# 2_5_0_PCB_LY-2X5_0-V1_1.net
KiCad netlist of a schematic drawn in EasyEDA Pro
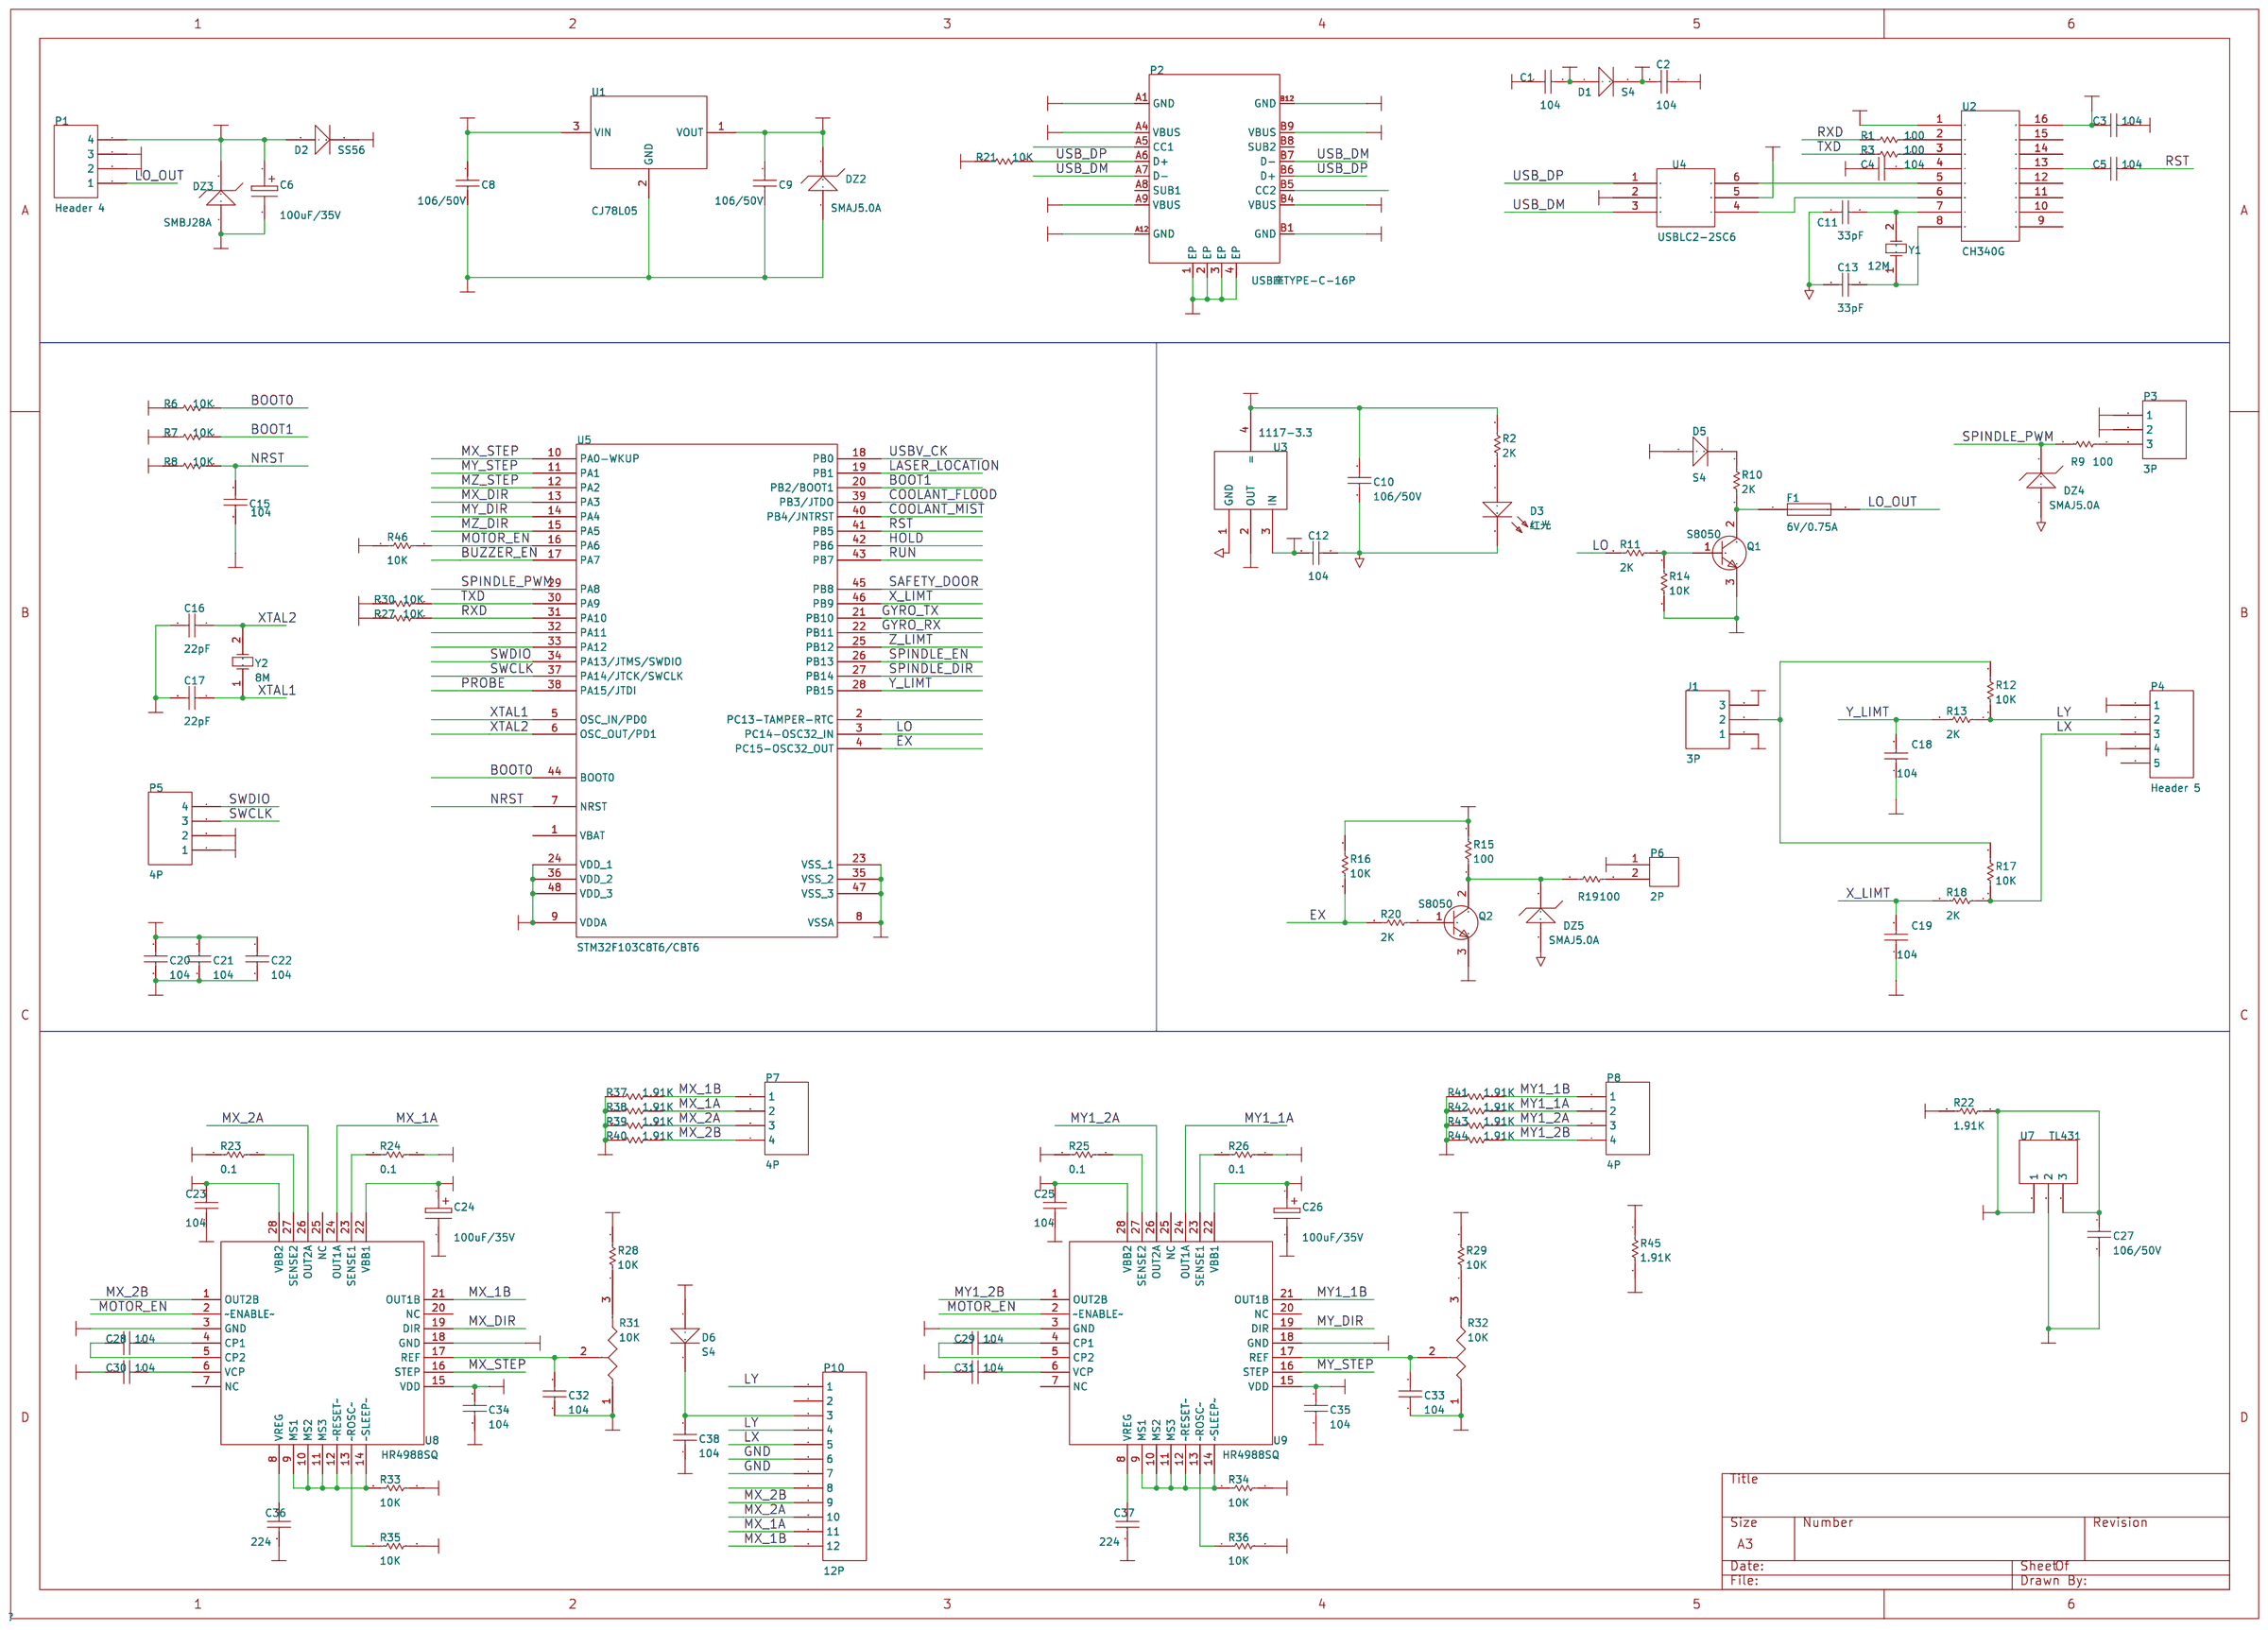
[diagram p0: schematic sheet]

(export (version "E")
  (design (tool "Eeschema 10.0.6"))
  (components
    (comp (ref "C1")
      (value "104")
      (footprint "easyedapro:0603C")
      (description "Capacitor (Semiconductor SIM Model)")
      (libsource (lib "easyedapro") (part "Cap Semi"))
    )
    (comp (ref "C2")
      (value "104")
      (footprint "easyedapro:0603C")
      (description "Capacitor (Semiconductor SIM Model)")
      (libsource (lib "easyedapro") (part "Cap Semi"))
    )
    (comp (ref "C3")
      (value "104")
      (footprint "easyedapro:0603C")
      (description "Capacitor (Semiconductor SIM Model)")
      (libsource (lib "easyedapro") (part "Cap Semi"))
    )
    (comp (ref "C4")
      (value "104")
      (footprint "easyedapro:0603C")
      (description "Capacitor (Semiconductor SIM Model)")
      (libsource (lib "easyedapro") (part "Cap Semi"))
    )
    (comp (ref "C5")
      (value "104")
      (footprint "easyedapro:0603C")
      (description "Capacitor (Semiconductor SIM Model)")
      (libsource (lib "easyedapro") (part "Cap Semi"))
    )
    (comp (ref "C6")
      (value "100uF/35V")
      (footprint "easyedapro:电容插件M6.3")
      (libsource (lib "easyedapro") (part "ELECTRO1"))
    )
    (comp (ref "C8")
      (value "106/50V")
      (footprint "easyedapro:0603C")
      (description "Capacitor (Semiconductor SIM Model)")
      (libsource (lib "easyedapro") (part "Cap Semi"))
    )
    (comp (ref "C9")
      (value "106/50V")
      (footprint "easyedapro:0603C")
      (description "Capacitor (Semiconductor SIM Model)")
      (libsource (lib "easyedapro") (part "Cap Semi"))
    )
    (comp (ref "C10")
      (value "106/50V")
      (footprint "easyedapro:0603C")
      (description "Capacitor (Semiconductor SIM Model)")
      (libsource (lib "easyedapro") (part "Cap Semi"))
    )
    (comp (ref "C11")
      (value "18pF")
      (footprint "easyedapro:0603C")
      (description "Capacitor (Semiconductor SIM Model)")
      (libsource (lib "easyedapro") (part "Cap Semi"))
    )
    (comp (ref "C12")
      (value "104")
      (footprint "easyedapro:0603C")
      (description "Capacitor (Semiconductor SIM Model)")
      (libsource (lib "easyedapro") (part "Cap Semi"))
    )
    (comp (ref "C13")
      (value "18pF")
      (footprint "easyedapro:0603C")
      (description "Capacitor (Semiconductor SIM Model)")
      (libsource (lib "easyedapro") (part "Cap Semi"))
    )
    (comp (ref "C15")
      (value "104")
      (footprint "easyedapro:0603C")
      (description "Capacitor (Semiconductor SIM Model)")
      (libsource (lib "easyedapro") (part "Cap Semi"))
    )
    (comp (ref "C16")
      (value "100pF")
      (footprint "easyedapro:0603C")
      (description "Capacitor (Semiconductor SIM Model)")
      (libsource (lib "easyedapro") (part "Cap Semi"))
    )
    (comp (ref "C17")
      (value "100pF")
      (footprint "easyedapro:0603C")
      (description "Capacitor (Semiconductor SIM Model)")
      (libsource (lib "easyedapro") (part "Cap Semi"))
    )
    (comp (ref "C18")
      (value "104")
      (footprint "easyedapro:0603C")
      (libsource (lib "easyedapro") (part "CAP"))
    )
    (comp (ref "C19")
      (value "104")
      (footprint "easyedapro:0603C")
      (libsource (lib "easyedapro") (part "CAP"))
    )
    (comp (ref "C20")
      (value "104")
      (footprint "easyedapro:0603C")
      (libsource (lib "easyedapro") (part "CAP"))
    )
    (comp (ref "C21")
      (value "104")
      (footprint "easyedapro:0603C")
      (libsource (lib "easyedapro") (part "CAP"))
    )
    (comp (ref "C22")
      (value "104")
      (footprint "easyedapro:0603C")
      (libsource (lib "easyedapro") (part "CAP"))
    )
    (comp (ref "C23")
      (value "104")
      (footprint "easyedapro:0603C")
      (description "Capacitor (Semiconductor SIM Model)")
      (libsource (lib "easyedapro") (part "Cap Semi"))
    )
    (comp (ref "C24")
      (value "100uF/35V")
      (footprint "easyedapro:电容插件M6.3")
      (libsource (lib "easyedapro") (part "ELECTRO1"))
    )
    (comp (ref "C25")
      (value "104")
      (footprint "easyedapro:0603C")
      (description "Capacitor (Semiconductor SIM Model)")
      (libsource (lib "easyedapro") (part "Cap Semi"))
    )
    (comp (ref "C26")
      (value "100uF/35V")
      (footprint "easyedapro:电容插件M6.3")
      (libsource (lib "easyedapro") (part "ELECTRO1"))
    )
    (comp (ref "C27")
      (value "106/50V")
      (footprint "easyedapro:0603C")
      (description "Capacitor (Semiconductor SIM Model)")
      (libsource (lib "easyedapro") (part "Cap Semi"))
    )
    (comp (ref "C28")
      (value "104")
      (footprint "easyedapro:0603C")
      (libsource (lib "easyedapro") (part "CAP"))
    )
    (comp (ref "C29")
      (value "104")
      (footprint "easyedapro:0603C")
      (libsource (lib "easyedapro") (part "CAP"))
    )
    (comp (ref "C30")
      (value "104")
      (footprint "easyedapro:0603C")
      (libsource (lib "easyedapro") (part "CAP"))
    )
    (comp (ref "C31")
      (value "104")
      (footprint "easyedapro:0603C")
      (libsource (lib "easyedapro") (part "CAP"))
    )
    (comp (ref "C32")
      (value "104")
      (footprint "easyedapro:0603C")
      (libsource (lib "easyedapro") (part "CAP"))
    )
    (comp (ref "C33")
      (value "104")
      (footprint "easyedapro:0603C")
      (libsource (lib "easyedapro") (part "CAP"))
    )
    (comp (ref "C34")
      (value "104")
      (footprint "easyedapro:0603C")
      (libsource (lib "easyedapro") (part "CAP"))
    )
    (comp (ref "C35")
      (value "104")
      (footprint "easyedapro:0603C")
      (libsource (lib "easyedapro") (part "CAP"))
    )
    (comp (ref "C36")
      (value "224")
      (footprint "easyedapro:0603C")
      (libsource (lib "easyedapro") (part "CAP"))
    )
    (comp (ref "C37")
      (value "224")
      (footprint "easyedapro:0603C")
      (libsource (lib "easyedapro") (part "CAP"))
    )
    (comp (ref "C38")
      (value "104")
      (footprint "easyedapro:0603C")
      (description "Capacitor (Semiconductor SIM Model)")
      (libsource (lib "easyedapro") (part "Cap Semi"))
    )
    (comp (ref "D1") (value "S4") (footprint "easyedapro:SMA") (libsource (lib "easyedapro") (part "1N4148")))
    (comp (ref "D2")
      (value "SS56")
      (footprint "easyedapro:SMA")
      (libsource (lib "easyedapro") (part "1N4148"))
    )
    (comp (ref "D3")
      (value "红光")
      (footprint "easyedapro:0603LED")
      (libsource (lib "easyedapro") (part "LED"))
    )
    (comp (ref "D5") (value "S4") (footprint "easyedapro:SMA") (libsource (lib "easyedapro") (part "1N4148")))
    (comp (ref "D6") (value "S4") (footprint "easyedapro:SMA") (libsource (lib "easyedapro") (part "1N4148")))
    (comp (ref "DZ2")
      (value "SMAJ5.0A")
      (footprint "easyedapro:SMA")
      (libsource (lib "easyedapro") (part "稳压二极管"))
    )
    (comp (ref "DZ3")
      (value "SMBJ28A")
      (footprint "easyedapro:SMA")
      (libsource (lib "easyedapro") (part "稳压二极管"))
    )
    (comp (ref "DZ4")
      (value "SMAJ5.0A")
      (footprint "easyedapro:SMA")
      (libsource (lib "easyedapro") (part "稳压二极管"))
    )
    (comp (ref "DZ5")
      (value "SMAJ5.0A")
      (footprint "easyedapro:SMA")
      (libsource (lib "easyedapro") (part "稳压二极管"))
    )
    (comp (ref "F1")
      (value "6V/0.75A")
      (footprint "easyedapro:1206R")
      (description "保险丝")
      (libsource (lib "easyedapro") (part "FUSE1"))
    )
    (comp (ref "J1")
      (value "3P")
      (footprint "easyedapro:HDR1X3_CON")
      (libsource (lib "easyedapro") (part "3P"))
    )
    (comp (ref "P1")
      (value "Header 4")
      (footprint "easyedapro:VH3.96-4P直插座")
      (description "Header, 4-Pin")
      (libsource (lib "easyedapro") (part "Header 4"))
    )
    (comp (ref "P2")
      (value "USB座TYPE-C-16P")
      (footprint "easyedapro:USB-TYPE-C-16P")
      (fields
        (field (name "Manufacturer Part") "KH-TYPE-C-16P-T")
        (field (name "Manufacturer") "Shenzhen Kinghelm Elec")
      )
      (libsource (lib "easyedapro") (part "USB座TYPE-C-16P"))
    )
    (comp (ref "P3")
      (value "3P")
      (footprint "easyedapro:HDR1X3_CON")
      (libsource (lib "easyedapro") (part "3P"))
    )
    (comp (ref "P4")
      (value "Header 5")
      (footprint "easyedapro:HDR1X5_CON")
      (description "Header, 5-Pin")
      (libsource (lib "easyedapro") (part "Header 5"))
    )
    (comp (ref "P5") (value "4P") (footprint "easyedapro:SIP4") (libsource (lib "easyedapro") (part "4P")))
    (comp (ref "P6")
      (value "2P")
      (footprint "easyedapro:HDR1X2_CON")
      (libsource (lib "easyedapro") (part "2P"))
    )
    (comp (ref "P7") (value "4P") (footprint "easyedapro:SIP4") (libsource (lib "easyedapro") (part "4P")))
    (comp (ref "P8") (value "4P") (footprint "easyedapro:SIP4") (libsource (lib "easyedapro") (part "4P")))
    (comp (ref "P10")
      (value "12P")
      (footprint "easyedapro:FFC/FPC直插座-1.25-12P")
      (libsource (lib "easyedapro") (part "12P"))
    )
    (comp (ref "Q1")
      (value "S8050")
      (footprint "easyedapro:SOT-23")
      (libsource (lib "easyedapro") (part "NPN"))
    )
    (comp (ref "Q2")
      (value "S8050")
      (footprint "easyedapro:SOT-23")
      (libsource (lib "easyedapro") (part "NPN"))
    )
    (comp (ref "R1")
      (value "100")
      (footprint "easyedapro:1206R")
      (description "Resistor")
      (libsource (lib "easyedapro") (part "RES"))
    )
    (comp (ref "R2")
      (value "2K")
      (footprint "easyedapro:1206R")
      (description "Resistor")
      (libsource (lib "easyedapro") (part "RES"))
    )
    (comp (ref "R3")
      (value "100")
      (footprint "easyedapro:1206R")
      (description "Resistor")
      (libsource (lib "easyedapro") (part "RES"))
    )
    (comp (ref "R6")
      (value "10K")
      (footprint "easyedapro:1206R")
      (description "Resistor")
      (libsource (lib "easyedapro") (part "RES"))
    )
    (comp (ref "R7")
      (value "10K")
      (footprint "easyedapro:1206R")
      (description "Resistor")
      (libsource (lib "easyedapro") (part "RES"))
    )
    (comp (ref "R8")
      (value "10K")
      (footprint "easyedapro:1206R")
      (description "Resistor")
      (libsource (lib "easyedapro") (part "RES"))
    )
    (comp (ref "R9")
      (value "100")
      (footprint "easyedapro:1206R")
      (description "Resistor")
      (libsource (lib "easyedapro") (part "RES"))
    )
    (comp (ref "R10")
      (value "2K")
      (footprint "easyedapro:1206R")
      (description "Resistor")
      (libsource (lib "easyedapro") (part "RES"))
    )
    (comp (ref "R11")
      (value "2K")
      (footprint "easyedapro:1206R")
      (description "Resistor")
      (libsource (lib "easyedapro") (part "RES"))
    )
    (comp (ref "R12")
      (value "10K")
      (footprint "easyedapro:1206R")
      (description "Resistor")
      (libsource (lib "easyedapro") (part "RES"))
    )
    (comp (ref "R13")
      (value "2K")
      (footprint "easyedapro:1206R")
      (description "Resistor")
      (libsource (lib "easyedapro") (part "RES"))
    )
    (comp (ref "R14")
      (value "10K")
      (footprint "easyedapro:1206R")
      (description "Resistor")
      (libsource (lib "easyedapro") (part "RES"))
    )
    (comp (ref "R15")
      (value "100")
      (footprint "easyedapro:1206R")
      (description "Resistor")
      (libsource (lib "easyedapro") (part "RES"))
    )
    (comp (ref "R16")
      (value "10K")
      (footprint "easyedapro:1206R")
      (description "Resistor")
      (libsource (lib "easyedapro") (part "RES"))
    )
    (comp (ref "R17")
      (value "10K")
      (footprint "easyedapro:1206R")
      (description "Resistor")
      (libsource (lib "easyedapro") (part "RES"))
    )
    (comp (ref "R18")
      (value "2K")
      (footprint "easyedapro:1206R")
      (description "Resistor")
      (libsource (lib "easyedapro") (part "RES"))
    )
    (comp (ref "R19")
      (value "100")
      (footprint "easyedapro:1206R")
      (description "Resistor")
      (libsource (lib "easyedapro") (part "RES"))
    )
    (comp (ref "R20")
      (value "2K")
      (footprint "easyedapro:1206R")
      (description "Resistor")
      (libsource (lib "easyedapro") (part "RES"))
    )
    (comp (ref "R21")
      (value "10K")
      (footprint "easyedapro:1206R")
      (description "Resistor")
      (libsource (lib "easyedapro") (part "RES"))
    )
    (comp (ref "R22")
      (value "1.91K")
      (footprint "easyedapro:1206R")
      (description "Resistor")
      (libsource (lib "easyedapro") (part "RES"))
    )
    (comp (ref "R23")
      (value "0.1")
      (footprint "easyedapro:1206R")
      (description "Resistor")
      (libsource (lib "easyedapro") (part "RES"))
    )
    (comp (ref "R24")
      (value "0.1")
      (footprint "easyedapro:1206R")
      (description "Resistor")
      (libsource (lib "easyedapro") (part "RES"))
    )
    (comp (ref "R25")
      (value "0.1")
      (footprint "easyedapro:1206R")
      (description "Resistor")
      (libsource (lib "easyedapro") (part "RES"))
    )
    (comp (ref "R26")
      (value "0.1")
      (footprint "easyedapro:1206R")
      (description "Resistor")
      (libsource (lib "easyedapro") (part "RES"))
    )
    (comp (ref "R27")
      (value "10K")
      (footprint "easyedapro:1206R")
      (description "Resistor")
      (libsource (lib "easyedapro") (part "RES"))
    )
    (comp (ref "R28")
      (value "10K")
      (footprint "easyedapro:1206R")
      (description "Resistor")
      (libsource (lib "easyedapro") (part "RES"))
    )
    (comp (ref "R29")
      (value "10K")
      (footprint "easyedapro:1206R")
      (description "Resistor")
      (libsource (lib "easyedapro") (part "RES"))
    )
    (comp (ref "R30")
      (value "10K")
      (footprint "easyedapro:1206R")
      (description "Resistor")
      (libsource (lib "easyedapro") (part "RES"))
    )
    (comp (ref "R31")
      (value "10K")
      (footprint "easyedapro:松下贴片电位器3x3")
      (libsource (lib "easyedapro") (part "电位器"))
    )
    (comp (ref "R32")
      (value "10K")
      (footprint "easyedapro:松下贴片电位器3x3")
      (libsource (lib "easyedapro") (part "电位器"))
    )
    (comp (ref "R33")
      (value "10K")
      (footprint "easyedapro:1206R")
      (description "Resistor")
      (libsource (lib "easyedapro") (part "RES"))
    )
    (comp (ref "R34")
      (value "10K")
      (footprint "easyedapro:1206R")
      (description "Resistor")
      (libsource (lib "easyedapro") (part "RES"))
    )
    (comp (ref "R35")
      (value "10K")
      (footprint "easyedapro:1206R")
      (description "Resistor")
      (libsource (lib "easyedapro") (part "RES"))
    )
    (comp (ref "R36")
      (value "10K")
      (footprint "easyedapro:1206R")
      (description "Resistor")
      (libsource (lib "easyedapro") (part "RES"))
    )
    (comp (ref "R37")
      (value "1.91K")
      (footprint "easyedapro:1206R")
      (description "Resistor")
      (libsource (lib "easyedapro") (part "RES"))
    )
    (comp (ref "R38")
      (value "1.91K")
      (footprint "easyedapro:1206R")
      (description "Resistor")
      (libsource (lib "easyedapro") (part "RES"))
    )
    (comp (ref "R39")
      (value "1.91K")
      (footprint "easyedapro:1206R")
      (description "Resistor")
      (libsource (lib "easyedapro") (part "RES"))
    )
    (comp (ref "R40")
      (value "1.91K")
      (footprint "easyedapro:1206R")
      (description "Resistor")
      (libsource (lib "easyedapro") (part "RES"))
    )
    (comp (ref "R41")
      (value "1.91K")
      (footprint "easyedapro:1206R")
      (description "Resistor")
      (libsource (lib "easyedapro") (part "RES"))
    )
    (comp (ref "R42")
      (value "1.91K")
      (footprint "easyedapro:1206R")
      (description "Resistor")
      (libsource (lib "easyedapro") (part "RES"))
    )
    (comp (ref "R43")
      (value "1.91K")
      (footprint "easyedapro:1206R")
      (description "Resistor")
      (libsource (lib "easyedapro") (part "RES"))
    )
    (comp (ref "R44")
      (value "1.91K")
      (footprint "easyedapro:1206R")
      (description "Resistor")
      (libsource (lib "easyedapro") (part "RES"))
    )
    (comp (ref "R45")
      (value "1.91K")
      (footprint "easyedapro:1206R")
      (description "Resistor")
      (libsource (lib "easyedapro") (part "RES"))
    )
    (comp (ref "R46")
      (value "10K")
      (footprint "easyedapro:1206R")
      (description "Resistor")
      (libsource (lib "easyedapro") (part "RES"))
    )
    (comp (ref "U1")
      (value "CJ78L05")
      (footprint "easyedapro:TO-263-2")
      (libsource (lib "easyedapro") (part "78L05"))
    )
    (comp (ref "U2")
      (value "CH340G")
      (footprint "easyedapro:SOP16")
      (libsource (lib "easyedapro") (part "DIP16"))
    )
    (comp (ref "U3")
      (value "1117-3.3")
      (footprint "easyedapro:SOT-223")
      (libsource (lib "easyedapro") (part "LM1117"))
    )
    (comp (ref "U4")
      (value "USBLC2-2SC6")
      (footprint "easyedapro:SOT-23-6")
      (libsource (lib "easyedapro") (part "DIP6"))
    )
    (comp (ref "U5")
      (value "STM32F103C8T6/CBT6")
      (footprint "easyedapro:LQFP48")
      (description "STM32 ARM-based 32-bit MCU with 32 Kbytes Flash, 48-pin LQFP, Industrial Temperature")
      (libsource (lib "easyedapro") (part "STM32F103C6T6"))
    )
    (comp (ref "U7")
      (value "TL431")
      (footprint "easyedapro:HDR1X3_CON")
      (libsource (lib "easyedapro") (part "3P"))
    )
    (comp (ref "U8")
      (value "HR4988SQ")
      (footprint "easyedapro:QFN28")
      (libsource (lib "easyedapro") (part "HR4988"))
    )
    (comp (ref "U9")
      (value "HR4988SQ")
      (footprint "easyedapro:QFN28")
      (libsource (lib "easyedapro") (part "HR4988"))
    )
    (comp (ref "Y1")
      (value "12M")
      (footprint "easyedapro:晶振贴片49SSMD")
      (description "Crystal Oscillator")
      (libsource (lib "easyedapro") (part "XTAL"))
    )
    (comp (ref "Y2")
      (value "8M")
      (footprint "easyedapro:晶振贴片49SSMD")
      (description "Crystal Oscillator")
      (libsource (lib "easyedapro") (part "XTAL"))
    )
  )
  (nets
    (net (code "1") (name "/BOOT0") (class "Default")
      (node (ref "R6") (pin "2") (pinfunction "2_2") (pintype "unspecified"))
      (node (ref "U5") (pin "44") (pinfunction "BOOT0_44") (pintype "input"))
    )
    (net (code "2") (name "/BOOT1") (class "Default")
      (node (ref "R7") (pin "2") (pinfunction "2_2") (pintype "unspecified"))
      (node (ref "U5") (pin "20") (pinfunction "PB2/BOOT1_20") (pintype "bidirectional"))
    )
    (net (code "3") (name "/BUZZER_EN") (class "Default")
      (node (ref "U5") (pin "17") (pinfunction "PA7_17") (pintype "bidirectional"))
    )
    (net (code "4") (name "/COOLANT_FLOOD") (class "Default")
      (node (ref "U5") (pin "39") (pinfunction "PB3/JTDO_39") (pintype "bidirectional"))
    )
    (net (code "5") (name "/COOLANT_MIST") (class "Default")
      (node (ref "U5") (pin "40") (pinfunction "PB4/JNTRST_40") (pintype "bidirectional"))
    )
    (net (code "6") (name "/EX") (class "Default")
      (node (ref "R16") (pin "2") (pinfunction "2_2") (pintype "unspecified"))
      (node (ref "R20") (pin "2") (pinfunction "2_2") (pintype "unspecified"))
      (node (ref "U5") (pin "4") (pinfunction "PC15-OSC32_OUT_4") (pintype "bidirectional"))
    )
    (net (code "7") (name "/GYRO_RX") (class "Default")
      (node (ref "U5") (pin "22") (pinfunction "PB11_22") (pintype "bidirectional"))
    )
    (net (code "8") (name "/GYRO_TX") (class "Default")
      (node (ref "U5") (pin "21") (pinfunction "PB10_21") (pintype "bidirectional"))
    )
    (net (code "9") (name "/HOLD") (class "Default")
      (node (ref "U5") (pin "42") (pinfunction "PB6_42") (pintype "bidirectional"))
    )
    (net (code "10") (name "/LASER_LOCATION") (class "Default")
      (node (ref "U5") (pin "19") (pinfunction "PB1_19") (pintype "bidirectional"))
    )
    (net (code "11") (name "/LO") (class "Default")
      (node (ref "R11") (pin "2") (pinfunction "2_2") (pintype "unspecified"))
      (node (ref "U5") (pin "3") (pinfunction "PC14-OSC32_IN_3") (pintype "bidirectional"))
    )
    (net (code "12") (name "/LO_OUT") (class "Default")
      (node (ref "F1") (pin "2") (pinfunction "2_2") (pintype "unspecified"))
      (node (ref "P1") (pin "1") (pinfunction "1_1") (pintype "unspecified"))
    )
    (net (code "13") (name "/LX") (class "Default")
      (node (ref "P10") (pin "5") (pinfunction "5_5") (pintype "unspecified"))
      (node (ref "P4") (pin "3") (pinfunction "3_3") (pintype "unspecified"))
      (node (ref "R17") (pin "2") (pinfunction "2_2") (pintype "unspecified"))
      (node (ref "R18") (pin "1") (pinfunction "1_1") (pintype "unspecified"))
    )
    (net (code "14") (name "/LY") (class "Default")
      (node (ref "P10") (pin "1") (pinfunction "1_1") (pintype "unspecified"))
      (node (ref "P10") (pin "4") (pinfunction "4_4") (pintype "unspecified"))
      (node (ref "P4") (pin "2") (pinfunction "2_2") (pintype "unspecified"))
      (node (ref "R12") (pin "1") (pinfunction "1_1") (pintype "unspecified"))
      (node (ref "R13") (pin "1") (pinfunction "1_1") (pintype "unspecified"))
    )
    (net (code "15") (name "/MOTOR_EN") (class "Default")
      (node (ref "R46") (pin "1") (pinfunction "1_1") (pintype "unspecified"))
      (node (ref "U5") (pin "16") (pinfunction "PA6_16") (pintype "bidirectional"))
      (node (ref "U8") (pin "2") (pinfunction "~ENABLE~_2") (pintype "unspecified"))
      (node (ref "U9") (pin "2") (pinfunction "~ENABLE~_2") (pintype "unspecified"))
    )
    (net (code "16") (name "/MX_1A") (class "Default")
      (node (ref "P10") (pin "11") (pinfunction "11_11") (pintype "unspecified"))
      (node (ref "P7") (pin "2") (pinfunction "2_2") (pintype "unspecified"))
      (node (ref "R38") (pin "1") (pinfunction "1_1") (pintype "unspecified"))
      (node (ref "U8") (pin "24") (pinfunction "OUT1A_24") (pintype "unspecified"))
    )
    (net (code "17") (name "/MX_1B") (class "Default")
      (node (ref "P10") (pin "12") (pinfunction "12_12") (pintype "unspecified"))
      (node (ref "P7") (pin "1") (pinfunction "1_1") (pintype "unspecified"))
      (node (ref "R37") (pin "1") (pinfunction "1_1") (pintype "unspecified"))
      (node (ref "U8") (pin "21") (pinfunction "OUT1B_21") (pintype "unspecified"))
    )
    (net (code "18") (name "/MX_2A") (class "Default")
      (node (ref "P10") (pin "10") (pinfunction "10_10") (pintype "unspecified"))
      (node (ref "P7") (pin "3") (pinfunction "3_3") (pintype "unspecified"))
      (node (ref "R39") (pin "1") (pinfunction "1_1") (pintype "unspecified"))
      (node (ref "U8") (pin "26") (pinfunction "OUT2A_26") (pintype "unspecified"))
    )
    (net (code "19") (name "/MX_2B") (class "Default")
      (node (ref "P10") (pin "9") (pinfunction "9_9") (pintype "unspecified"))
      (node (ref "P7") (pin "4") (pinfunction "4_4") (pintype "unspecified"))
      (node (ref "R40") (pin "1") (pinfunction "1_1") (pintype "unspecified"))
      (node (ref "U8") (pin "1") (pinfunction "OUT2B_1") (pintype "unspecified"))
    )
    (net (code "20") (name "/MX_DIR") (class "Default")
      (node (ref "U5") (pin "13") (pinfunction "PA3_13") (pintype "bidirectional"))
      (node (ref "U8") (pin "19") (pinfunction "DIR_19") (pintype "unspecified"))
    )
    (net (code "21") (name "/MX_STEP") (class "Default")
      (node (ref "U5") (pin "10") (pinfunction "PA0-WKUP_10") (pintype "bidirectional"))
      (node (ref "U8") (pin "16") (pinfunction "STEP_16") (pintype "unspecified"))
    )
    (net (code "22") (name "/MY1_1A") (class "Default")
      (node (ref "P8") (pin "2") (pinfunction "2_2") (pintype "unspecified"))
      (node (ref "R42") (pin "1") (pinfunction "1_1") (pintype "unspecified"))
      (node (ref "U9") (pin "24") (pinfunction "OUT1A_24") (pintype "unspecified"))
    )
    (net (code "23") (name "/MY1_1B") (class "Default")
      (node (ref "P8") (pin "1") (pinfunction "1_1") (pintype "unspecified"))
      (node (ref "R41") (pin "1") (pinfunction "1_1") (pintype "unspecified"))
      (node (ref "U9") (pin "21") (pinfunction "OUT1B_21") (pintype "unspecified"))
    )
    (net (code "24") (name "/MY1_2A") (class "Default")
      (node (ref "P8") (pin "3") (pinfunction "3_3") (pintype "unspecified"))
      (node (ref "R43") (pin "1") (pinfunction "1_1") (pintype "unspecified"))
      (node (ref "U9") (pin "26") (pinfunction "OUT2A_26") (pintype "unspecified"))
    )
    (net (code "25") (name "/MY1_2B") (class "Default")
      (node (ref "P8") (pin "4") (pinfunction "4_4") (pintype "unspecified"))
      (node (ref "R44") (pin "1") (pinfunction "1_1") (pintype "unspecified"))
      (node (ref "U9") (pin "1") (pinfunction "OUT2B_1") (pintype "unspecified"))
    )
    (net (code "26") (name "/MY_DIR") (class "Default")
      (node (ref "U5") (pin "14") (pinfunction "PA4_14") (pintype "bidirectional"))
      (node (ref "U9") (pin "19") (pinfunction "DIR_19") (pintype "unspecified"))
    )
    (net (code "27") (name "/MY_STEP") (class "Default")
      (node (ref "U5") (pin "11") (pinfunction "PA1_11") (pintype "bidirectional"))
      (node (ref "U9") (pin "16") (pinfunction "STEP_16") (pintype "unspecified"))
    )
    (net (code "28") (name "/MZ_DIR") (class "Default")
      (node (ref "U5") (pin "15") (pinfunction "PA5_15") (pintype "bidirectional"))
    )
    (net (code "29") (name "/MZ_STEP") (class "Default")
      (node (ref "U5") (pin "12") (pinfunction "PA2_12") (pintype "bidirectional"))
    )
    (net (code "30") (name "/NRST") (class "Default")
      (node (ref "C15") (pin "2") (pinfunction "2_2") (pintype "unspecified"))
      (node (ref "R8") (pin "2") (pinfunction "2_2") (pintype "unspecified"))
      (node (ref "U5") (pin "7") (pinfunction "NRST_7") (pintype "bidirectional"))
    )
    (net (code "31") (name "/PROBE") (class "Default")
      (node (ref "U5") (pin "38") (pinfunction "PA15/JTDI_38") (pintype "bidirectional"))
    )
    (net (code "32") (name "/RST") (class "Default")
      (node (ref "C5") (pin "2") (pinfunction "2_2") (pintype "unspecified"))
      (node (ref "U5") (pin "41") (pinfunction "PB5_41") (pintype "bidirectional"))
    )
    (net (code "33") (name "/RUN") (class "Default")
      (node (ref "U5") (pin "43") (pinfunction "PB7_43") (pintype "bidirectional"))
    )
    (net (code "34") (name "/RXD") (class "Default")
      (node (ref "R1") (pin "2") (pinfunction "2_2") (pintype "unspecified"))
      (node (ref "R27") (pin "2") (pinfunction "2_2") (pintype "unspecified"))
      (node (ref "U5") (pin "31") (pinfunction "PA10_31") (pintype "bidirectional"))
    )
    (net (code "35") (name "/SAFETY_DOOR") (class "Default")
      (node (ref "U5") (pin "45") (pinfunction "PB8_45") (pintype "bidirectional"))
    )
    (net (code "36") (name "/SPINDLE_DIR") (class "Default")
      (node (ref "U5") (pin "27") (pinfunction "PB14_27") (pintype "bidirectional"))
    )
    (net (code "37") (name "/SPINDLE_EN") (class "Default")
      (node (ref "U5") (pin "26") (pinfunction "PB13_26") (pintype "bidirectional"))
    )
    (net (code "38") (name "/SPINDLE_PWM") (class "Default")
      (node (ref "DZ4") (pin "2") (pinfunction "2_2") (pintype "unspecified"))
      (node (ref "R9") (pin "2") (pinfunction "2_2") (pintype "unspecified"))
      (node (ref "U5") (pin "29") (pinfunction "PA8_29") (pintype "bidirectional"))
    )
    (net (code "39") (name "/SWCLK") (class "Default")
      (node (ref "P5") (pin "3") (pinfunction "3_3") (pintype "unspecified"))
      (node (ref "U5") (pin "37") (pinfunction "PA14/JTCK/SWCLK_37") (pintype "bidirectional"))
    )
    (net (code "40") (name "/SWDIO") (class "Default")
      (node (ref "P5") (pin "4") (pinfunction "4_4") (pintype "unspecified"))
      (node (ref "U5") (pin "34") (pinfunction "PA13/JTMS/SWDIO_34") (pintype "bidirectional"))
    )
    (net (code "41") (name "/TXD") (class "Default")
      (node (ref "R3") (pin "2") (pinfunction "2_2") (pintype "unspecified"))
      (node (ref "R30") (pin "2") (pinfunction "2_2") (pintype "unspecified"))
      (node (ref "U5") (pin "30") (pinfunction "PA9_30") (pintype "bidirectional"))
    )
    (net (code "42") (name "/USBV_CK") (class "Default")
      (node (ref "U5") (pin "18") (pinfunction "PB0_18") (pintype "bidirectional"))
    )
    (net (code "43") (name "/USB_DM") (class "Default")
      (node (ref "P2") (pin "A7") (pinfunction "D-_A7") (pintype "unspecified"))
      (node (ref "P2") (pin "B7") (pinfunction "D-_B7") (pintype "unspecified"))
      (node (ref "U4") (pin "3") (pinfunction "3_3") (pintype "unspecified"))
    )
    (net (code "44") (name "/USB_DP") (class "Default")
      (node (ref "P2") (pin "A6") (pinfunction "D+_A6") (pintype "unspecified"))
      (node (ref "P2") (pin "B6") (pinfunction "D+_B6") (pintype "unspecified"))
      (node (ref "R21") (pin "2") (pinfunction "2_2") (pintype "unspecified"))
      (node (ref "U4") (pin "1") (pinfunction "1_1") (pintype "unspecified"))
    )
    (net (code "45") (name "/XTAL1") (class "Default")
      (node (ref "C17") (pin "1") (pinfunction "1_1") (pintype "unspecified"))
      (node (ref "U5") (pin "5") (pinfunction "OSC_IN/PD0_5") (pintype "input"))
      (node (ref "Y2") (pin "1") (pinfunction "OSC1_1") (pintype "unspecified"))
    )
    (net (code "46") (name "/XTAL2") (class "Default")
      (node (ref "C16") (pin "1") (pinfunction "1_1") (pintype "unspecified"))
      (node (ref "U5") (pin "6") (pinfunction "OSC_OUT/PD1_6") (pintype "output"))
      (node (ref "Y2") (pin "2") (pinfunction "OSC2_2") (pintype "unspecified"))
    )
    (net (code "47") (name "/X_LIMT") (class "Default")
      (node (ref "C19") (pin "2") (pinfunction "2_2") (pintype "unspecified"))
      (node (ref "R18") (pin "2") (pinfunction "2_2") (pintype "unspecified"))
      (node (ref "U5") (pin "46") (pinfunction "PB9_46") (pintype "bidirectional"))
    )
    (net (code "48") (name "/Y_LIMT") (class "Default")
      (node (ref "C18") (pin "2") (pinfunction "2_2") (pintype "unspecified"))
      (node (ref "R13") (pin "2") (pinfunction "2_2") (pintype "unspecified"))
      (node (ref "U5") (pin "28") (pinfunction "PB15_28") (pintype "bidirectional"))
    )
    (net (code "49") (name "/Z_LIMT") (class "Default")
      (node (ref "U5") (pin "25") (pinfunction "PB12_25") (pintype "bidirectional"))
    )
    (net (code "50") (name "2.5V") (class "Default")
      (node (ref "C27") (pin "1") (pinfunction "1_1") (pintype "unspecified"))
      (node (ref "R22") (pin "1") (pinfunction "1_1") (pintype "unspecified"))
      (node (ref "R28") (pin "2") (pinfunction "2_2") (pintype "unspecified"))
      (node (ref "R29") (pin "2") (pinfunction "2_2") (pintype "unspecified"))
      (node (ref "U7") (pin "1") (pinfunction "1_1") (pintype "unspecified"))
      (node (ref "U7") (pin "3") (pinfunction "3_3") (pintype "unspecified"))
    )
    (net (code "51") (name "3V3") (class "Default")
      (node (ref "C10") (pin "1") (pinfunction "1_1") (pintype "unspecified"))
      (node (ref "C20") (pin "2") (pinfunction "2_2") (pintype "unspecified"))
      (node (ref "C21") (pin "2") (pinfunction "2_2") (pintype "unspecified"))
      (node (ref "C22") (pin "2") (pinfunction "2_2") (pintype "unspecified"))
      (node (ref "P5") (pin "2") (pinfunction "2_2") (pintype "unspecified"))
      (node (ref "R2") (pin "1") (pinfunction "1_1") (pintype "unspecified"))
      (node (ref "R27") (pin "1") (pinfunction "1_1") (pintype "unspecified"))
      (node (ref "R30") (pin "1") (pinfunction "1_1") (pintype "unspecified"))
      (node (ref "R46") (pin "2") (pinfunction "2_2") (pintype "unspecified"))
      (node (ref "R8") (pin "1") (pinfunction "1_1") (pintype "unspecified"))
      (node (ref "U3") (pin "2") (pinfunction "OUT_2") (pintype "unspecified"))
      (node (ref "U3") (pin "4") (pinfunction "=_4") (pintype "unspecified"))
      (node (ref "U5") (pin "24") (pinfunction "VDD_1_24") (pintype "unspecified"))
      (node (ref "U5") (pin "36") (pinfunction "VDD_2_36") (pintype "unspecified"))
      (node (ref "U5") (pin "48") (pinfunction "VDD_3_48") (pintype "unspecified"))
      (node (ref "U5") (pin "9") (pinfunction "VDDA_9") (pintype "unspecified"))
    )
    (net (code "52") (name "5VV") (class "Default")
      (node (ref "D6") (pin "1") (pinfunction "1_1") (pintype "unspecified"))
      (node (ref "P1") (pin "2") (pinfunction "2_2") (pintype "unspecified"))
    )
    (net (code "53") (name "24V") (class "Default")
      (node (ref "C8") (pin "1") (pinfunction "1_1") (pintype "unspecified"))
      (node (ref "D2") (pin "2") (pinfunction "2_2") (pintype "unspecified"))
      (node (ref "U1") (pin "3") (pinfunction "VIN_3") (pintype "unspecified"))
    )
    (net (code "54") (name "GND") (class "Default")
      (node (ref "C1") (pin "1") (pinfunction "1_1") (pintype "unspecified"))
      (node (ref "C10") (pin "2") (pinfunction "2_2") (pintype "unspecified"))
      (node (ref "C11") (pin "2") (pinfunction "2_2") (pintype "unspecified"))
      (node (ref "C12") (pin "1") (pinfunction "1_1") (pintype "unspecified"))
      (node (ref "C13") (pin "2") (pinfunction "2_2") (pintype "unspecified"))
      (node (ref "C15") (pin "1") (pinfunction "1_1") (pintype "unspecified"))
      (node (ref "C16") (pin "2") (pinfunction "2_2") (pintype "unspecified"))
      (node (ref "C17") (pin "2") (pinfunction "2_2") (pintype "unspecified"))
      (node (ref "C18") (pin "1") (pinfunction "1_1") (pintype "unspecified"))
      (node (ref "C19") (pin "1") (pinfunction "1_1") (pintype "unspecified"))
      (node (ref "C2") (pin "1") (pinfunction "1_1") (pintype "unspecified"))
      (node (ref "C20") (pin "1") (pinfunction "1_1") (pintype "unspecified"))
      (node (ref "C21") (pin "1") (pinfunction "1_1") (pintype "unspecified"))
      (node (ref "C22") (pin "1") (pinfunction "1_1") (pintype "unspecified"))
      (node (ref "C23") (pin "1") (pinfunction "1_1") (pintype "unspecified"))
      (node (ref "C24") (pin "2") (pintype "unspecified"))
      (node (ref "C25") (pin "1") (pinfunction "1_1") (pintype "unspecified"))
      (node (ref "C26") (pin "2") (pintype "unspecified"))
      (node (ref "C27") (pin "2") (pinfunction "2_2") (pintype "unspecified"))
      (node (ref "C3") (pin "2") (pinfunction "2_2") (pintype "unspecified"))
      (node (ref "C32") (pin "2") (pinfunction "2_2") (pintype "unspecified"))
      (node (ref "C33") (pin "2") (pinfunction "2_2") (pintype "unspecified"))
      (node (ref "C34") (pin "2") (pinfunction "2_2") (pintype "unspecified"))
      (node (ref "C35") (pin "2") (pinfunction "2_2") (pintype "unspecified"))
      (node (ref "C36") (pin "2") (pinfunction "2_2") (pintype "unspecified"))
      (node (ref "C37") (pin "2") (pinfunction "2_2") (pintype "unspecified"))
      (node (ref "C38") (pin "1") (pinfunction "1_1") (pintype "unspecified"))
      (node (ref "C4") (pin "2") (pinfunction "2_2") (pintype "unspecified"))
      (node (ref "C6") (pin "2") (pintype "unspecified"))
      (node (ref "C8") (pin "2") (pinfunction "2_2") (pintype "unspecified"))
      (node (ref "C9") (pin "2") (pinfunction "2_2") (pintype "unspecified"))
      (node (ref "D3") (pin "2") (pinfunction "2_2") (pintype "unspecified"))
      (node (ref "DZ2") (pin "1") (pinfunction "1_1") (pintype "unspecified"))
      (node (ref "DZ3") (pin "1") (pinfunction "1_1") (pintype "unspecified"))
      (node (ref "DZ4") (pin "1") (pinfunction "1_1") (pintype "unspecified"))
      (node (ref "DZ5") (pin "1") (pinfunction "1_1") (pintype "unspecified"))
      (node (ref "J1") (pin "1") (pinfunction "1_1") (pintype "unspecified"))
      (node (ref "P1") (pin "3") (pinfunction "3_3") (pintype "unspecified"))
      (node (ref "P10") (pin "6") (pinfunction "6_6") (pintype "unspecified"))
      (node (ref "P10") (pin "7") (pinfunction "7_7") (pintype "unspecified"))
      (node (ref "P2") (pin "1") (pinfunction "EP_1") (pintype "unspecified"))
      (node (ref "P2") (pin "2") (pinfunction "EP_2") (pintype "unspecified"))
      (node (ref "P2") (pin "3") (pinfunction "EP_3") (pintype "unspecified"))
      (node (ref "P2") (pin "4") (pinfunction "EP_4") (pintype "unspecified"))
      (node (ref "P2") (pin "A1") (pinfunction "GND_A1") (pintype "unspecified"))
      (node (ref "P2") (pin "A12") (pinfunction "GND_A12") (pintype "unspecified"))
      (node (ref "P2") (pin "B1") (pinfunction "GND_B1") (pintype "unspecified"))
      (node (ref "P2") (pin "B12") (pinfunction "GND_B12") (pintype "unspecified"))
      (node (ref "P3") (pin "2") (pinfunction "2_2") (pintype "unspecified"))
      (node (ref "P4") (pin "1") (pinfunction "1_1") (pintype "unspecified"))
      (node (ref "P4") (pin "4") (pinfunction "4_4") (pintype "unspecified"))
      (node (ref "P5") (pin "1") (pinfunction "1_1") (pintype "unspecified"))
      (node (ref "P6") (pin "1") (pintype "unspecified"))
      (node (ref "Q1") (pin "3") (pinfunction "E_3") (pintype "unspecified"))
      (node (ref "Q2") (pin "3") (pinfunction "E_3") (pintype "unspecified"))
      (node (ref "R14") (pin "2") (pinfunction "2_2") (pintype "unspecified"))
      (node (ref "R23") (pin "2") (pinfunction "2_2") (pintype "unspecified"))
      (node (ref "R24") (pin "1") (pinfunction "1_1") (pintype "unspecified"))
      (node (ref "R25") (pin "2") (pinfunction "2_2") (pintype "unspecified"))
      (node (ref "R26") (pin "1") (pinfunction "1_1") (pintype "unspecified"))
      (node (ref "R31") (pin "1") (pinfunction "A_1") (pintype "unspecified"))
      (node (ref "R32") (pin "1") (pinfunction "A_1") (pintype "unspecified"))
      (node (ref "R35") (pin "2") (pinfunction "2_2") (pintype "unspecified"))
      (node (ref "R36") (pin "2") (pinfunction "2_2") (pintype "unspecified"))
      (node (ref "R37") (pin "2") (pinfunction "2_2") (pintype "unspecified"))
      (node (ref "R38") (pin "2") (pinfunction "2_2") (pintype "unspecified"))
      (node (ref "R39") (pin "2") (pinfunction "2_2") (pintype "unspecified"))
      (node (ref "R40") (pin "2") (pinfunction "2_2") (pintype "unspecified"))
      (node (ref "R41") (pin "2") (pinfunction "2_2") (pintype "unspecified"))
      (node (ref "R42") (pin "2") (pinfunction "2_2") (pintype "unspecified"))
      (node (ref "R43") (pin "2") (pinfunction "2_2") (pintype "unspecified"))
      (node (ref "R44") (pin "2") (pinfunction "2_2") (pintype "unspecified"))
      (node (ref "R45") (pin "2") (pinfunction "2_2") (pintype "unspecified"))
      (node (ref "R6") (pin "1") (pinfunction "1_1") (pintype "unspecified"))
      (node (ref "R7") (pin "1") (pinfunction "1_1") (pintype "unspecified"))
      (node (ref "U1") (pin "2") (pinfunction "GND_2") (pintype "unspecified"))
      (node (ref "U2") (pin "1") (pinfunction "1_1") (pintype "unspecified"))
      (node (ref "U3") (pin "1") (pinfunction "GND_1") (pintype "unspecified"))
      (node (ref "U4") (pin "2") (pinfunction "2_2") (pintype "unspecified"))
      (node (ref "U5") (pin "23") (pinfunction "VSS_1_23") (pintype "unspecified"))
      (node (ref "U5") (pin "35") (pinfunction "VSS_2_35") (pintype "unspecified"))
      (node (ref "U5") (pin "47") (pinfunction "VSS_3_47") (pintype "unspecified"))
      (node (ref "U5") (pin "8") (pinfunction "VSSA_8") (pintype "unspecified"))
      (node (ref "U7") (pin "2") (pinfunction "2_2") (pintype "unspecified"))
      (node (ref "U8") (pin "18") (pinfunction "GND_18") (pintype "unspecified"))
      (node (ref "U8") (pin "3") (pinfunction "GND_3") (pintype "unspecified"))
      (node (ref "U9") (pin "18") (pinfunction "GND_18") (pintype "unspecified"))
      (node (ref "U9") (pin "3") (pinfunction "GND_3") (pintype "unspecified"))
    )
    (net (code "55") (name "Net-(C4-Pad1)") (class "Default")
      (node (ref "C4") (pin "1") (pinfunction "1_1") (pintype "unspecified"))
      (node (ref "U2") (pin "4") (pinfunction "4_4") (pintype "unspecified"))
    )
    (net (code "56") (name "Net-(C5-Pad1)") (class "Default")
      (node (ref "C5") (pin "1") (pinfunction "1_1") (pintype "unspecified"))
      (node (ref "U2") (pin "13") (pinfunction "13_13") (pintype "unspecified"))
    )
    (net (code "57") (name "Net-(C38-Pad2)") (class "Default")
      (node (ref "C38") (pin "2") (pinfunction "2_2") (pintype "unspecified"))
      (node (ref "D6") (pin "2") (pinfunction "2_2") (pintype "unspecified"))
      (node (ref "P10") (pin "3") (pinfunction "3_3") (pintype "unspecified"))
    )
    (net (code "58") (name "Net-(D3-Pad1)") (class "Default")
      (node (ref "D3") (pin "1") (pinfunction "1_1") (pintype "unspecified"))
      (node (ref "R2") (pin "2") (pinfunction "2_2") (pintype "unspecified"))
    )
    (net (code "59") (name "Net-(D5-Pad2)") (class "Default")
      (node (ref "D5") (pin "2") (pinfunction "2_2") (pintype "unspecified"))
      (node (ref "R10") (pin "1") (pinfunction "1_1") (pintype "unspecified"))
    )
    (net (code "60") (name "Net-(J1-Pad2)") (class "Default")
      (node (ref "J1") (pin "2") (pinfunction "2_2") (pintype "unspecified"))
      (node (ref "R12") (pin "2") (pinfunction "2_2") (pintype "unspecified"))
      (node (ref "R17") (pin "1") (pinfunction "1_1") (pintype "unspecified"))
    )
    (net (code "61") (name "Net-(P3-Pad3)") (class "Default")
      (node (ref "P3") (pin "3") (pinfunction "3_3") (pintype "unspecified"))
      (node (ref "R9") (pin "1") (pinfunction "1_1") (pintype "unspecified"))
    )
    (net (code "62") (name "Net-(P6-Pad2)") (class "Default")
      (node (ref "P6") (pin "2") (pintype "unspecified"))
      (node (ref "R19") (pin "1") (pinfunction "1_1") (pintype "unspecified"))
    )
    (net (code "63") (name "Net-(Q1-B)") (class "Default")
      (node (ref "Q1") (pin "1") (pinfunction "B_1") (pintype "unspecified"))
      (node (ref "R11") (pin "1") (pinfunction "1_1") (pintype "unspecified"))
      (node (ref "R14") (pin "1") (pinfunction "1_1") (pintype "unspecified"))
    )
    (net (code "64") (name "Net-(Q1-C)") (class "Default")
      (node (ref "F1") (pin "1") (pinfunction "1_1") (pintype "unspecified"))
      (node (ref "Q1") (pin "2") (pinfunction "C_2") (pintype "unspecified"))
      (node (ref "R10") (pin "2") (pinfunction "2_2") (pintype "unspecified"))
    )
    (net (code "65") (name "Net-(Q2-B)") (class "Default")
      (node (ref "Q2") (pin "1") (pinfunction "B_1") (pintype "unspecified"))
      (node (ref "R20") (pin "1") (pinfunction "1_1") (pintype "unspecified"))
    )
    (net (code "66") (name "Net-(Q2-C)") (class "Default")
      (node (ref "DZ5") (pin "2") (pinfunction "2_2") (pintype "unspecified"))
      (node (ref "Q2") (pin "2") (pinfunction "C_2") (pintype "unspecified"))
      (node (ref "R15") (pin "2") (pinfunction "2_2") (pintype "unspecified"))
      (node (ref "R19") (pin "2") (pinfunction "2_2") (pintype "unspecified"))
    )
    (net (code "67") (name "Net-(R1-Pad1)") (class "Default")
      (node (ref "R1") (pin "1") (pinfunction "1_1") (pintype "unspecified"))
      (node (ref "U2") (pin "2") (pinfunction "2_2") (pintype "unspecified"))
    )
    (net (code "68") (name "Net-(R3-Pad1)") (class "Default")
      (node (ref "R3") (pin "1") (pinfunction "1_1") (pintype "unspecified"))
      (node (ref "U2") (pin "3") (pinfunction "3_3") (pintype "unspecified"))
    )
    (net (code "69") (name "Net-(R31-B)") (class "Default")
      (node (ref "R28") (pin "1") (pinfunction "1_1") (pintype "unspecified"))
      (node (ref "R31") (pin "3") (pinfunction "B_3") (pintype "unspecified"))
    )
    (net (code "70") (name "Net-(R31-TAP)") (class "Default")
      (node (ref "C32") (pin "1") (pinfunction "1_1") (pintype "unspecified"))
      (node (ref "R31") (pin "2") (pinfunction "TAP_2") (pintype "unspecified"))
      (node (ref "U8") (pin "17") (pinfunction "REF_17") (pintype "unspecified"))
    )
    (net (code "71") (name "Net-(R32-B)") (class "Default")
      (node (ref "R29") (pin "1") (pinfunction "1_1") (pintype "unspecified"))
      (node (ref "R32") (pin "3") (pinfunction "B_3") (pintype "unspecified"))
    )
    (net (code "72") (name "Net-(R32-TAP)") (class "Default")
      (node (ref "C33") (pin "1") (pinfunction "1_1") (pintype "unspecified"))
      (node (ref "R32") (pin "2") (pinfunction "TAP_2") (pintype "unspecified"))
      (node (ref "U9") (pin "17") (pinfunction "REF_17") (pintype "unspecified"))
    )
    (net (code "73") (name "Net-(U2-Pad5)") (class "Default")
      (node (ref "U2") (pin "5") (pinfunction "5_5") (pintype "unspecified"))
      (node (ref "U4") (pin "6") (pinfunction "6_6") (pintype "unspecified"))
    )
    (net (code "74") (name "Net-(U2-Pad6)") (class "Default")
      (node (ref "U2") (pin "6") (pinfunction "6_6") (pintype "unspecified"))
      (node (ref "U4") (pin "4") (pinfunction "4_4") (pintype "unspecified"))
    )
    (net (code "75") (name "Net-(U8-CP1)") (class "Default")
      (node (ref "C28") (pin "1") (pinfunction "1_1") (pintype "unspecified"))
      (node (ref "U8") (pin "4") (pinfunction "CP1_4") (pintype "unspecified"))
    )
    (net (code "76") (name "Net-(U8-CP2)") (class "Default")
      (node (ref "C28") (pin "2") (pinfunction "2_2") (pintype "unspecified"))
      (node (ref "U8") (pin "5") (pinfunction "CP2_5") (pintype "unspecified"))
    )
    (net (code "77") (name "Net-(U8-MS1)") (class "Default")
      (node (ref "R33") (pin "2") (pinfunction "2_2") (pintype "unspecified"))
      (node (ref "U8") (pin "10") (pinfunction "MS2_10") (pintype "unspecified"))
      (node (ref "U8") (pin "11") (pinfunction "MS3_11") (pintype "unspecified"))
      (node (ref "U8") (pin "12") (pinfunction "~RESET~_12") (pintype "unspecified"))
      (node (ref "U8") (pin "14") (pinfunction "~SLEEP~_14") (pintype "unspecified"))
      (node (ref "U8") (pin "9") (pinfunction "MS1_9") (pintype "unspecified"))
    )
    (net (code "78") (name "Net-(U8-SENSE1)") (class "Default")
      (node (ref "R24") (pin "2") (pinfunction "2_2") (pintype "unspecified"))
      (node (ref "U8") (pin "23") (pinfunction "SENSE1_23") (pintype "unspecified"))
    )
    (net (code "79") (name "Net-(U8-SENSE2)") (class "Default")
      (node (ref "R23") (pin "1") (pinfunction "1_1") (pintype "unspecified"))
      (node (ref "U8") (pin "27") (pinfunction "SENSE2_27") (pintype "unspecified"))
    )
    (net (code "80") (name "Net-(U8-VCP)") (class "Default")
      (node (ref "C30") (pin "1") (pinfunction "1_1") (pintype "unspecified"))
      (node (ref "U8") (pin "6") (pinfunction "VCP_6") (pintype "unspecified"))
    )
    (net (code "81") (name "Net-(U8-VREG)") (class "Default")
      (node (ref "C36") (pin "1") (pinfunction "1_1") (pintype "unspecified"))
      (node (ref "U8") (pin "8") (pinfunction "VREG_8") (pintype "unspecified"))
    )
    (net (code "82") (name "Net-(U8-~ROSC~)") (class "Default")
      (node (ref "R35") (pin "1") (pinfunction "1_1") (pintype "unspecified"))
      (node (ref "U8") (pin "13") (pinfunction "~ROSC~_13") (pintype "unspecified"))
    )
    (net (code "83") (name "Net-(U9-CP1)") (class "Default")
      (node (ref "C29") (pin "1") (pinfunction "1_1") (pintype "unspecified"))
      (node (ref "U9") (pin "4") (pinfunction "CP1_4") (pintype "unspecified"))
    )
    (net (code "84") (name "Net-(U9-CP2)") (class "Default")
      (node (ref "C29") (pin "2") (pinfunction "2_2") (pintype "unspecified"))
      (node (ref "U9") (pin "5") (pinfunction "CP2_5") (pintype "unspecified"))
    )
    (net (code "85") (name "Net-(U9-MS1)") (class "Default")
      (node (ref "R34") (pin "2") (pinfunction "2_2") (pintype "unspecified"))
      (node (ref "U9") (pin "10") (pinfunction "MS2_10") (pintype "unspecified"))
      (node (ref "U9") (pin "11") (pinfunction "MS3_11") (pintype "unspecified"))
      (node (ref "U9") (pin "12") (pinfunction "~RESET~_12") (pintype "unspecified"))
      (node (ref "U9") (pin "14") (pinfunction "~SLEEP~_14") (pintype "unspecified"))
      (node (ref "U9") (pin "9") (pinfunction "MS1_9") (pintype "unspecified"))
    )
    (net (code "86") (name "Net-(U9-SENSE1)") (class "Default")
      (node (ref "R26") (pin "2") (pinfunction "2_2") (pintype "unspecified"))
      (node (ref "U9") (pin "23") (pinfunction "SENSE1_23") (pintype "unspecified"))
    )
    (net (code "87") (name "Net-(U9-SENSE2)") (class "Default")
      (node (ref "R25") (pin "1") (pinfunction "1_1") (pintype "unspecified"))
      (node (ref "U9") (pin "27") (pinfunction "SENSE2_27") (pintype "unspecified"))
    )
    (net (code "88") (name "Net-(U9-VCP)") (class "Default")
      (node (ref "C31") (pin "1") (pinfunction "1_1") (pintype "unspecified"))
      (node (ref "U9") (pin "6") (pinfunction "VCP_6") (pintype "unspecified"))
    )
    (net (code "89") (name "Net-(U9-VREG)") (class "Default")
      (node (ref "C37") (pin "1") (pinfunction "1_1") (pintype "unspecified"))
      (node (ref "U9") (pin "8") (pinfunction "VREG_8") (pintype "unspecified"))
    )
    (net (code "90") (name "Net-(U9-~ROSC~)") (class "Default")
      (node (ref "R36") (pin "1") (pinfunction "1_1") (pintype "unspecified"))
      (node (ref "U9") (pin "13") (pinfunction "~ROSC~_13") (pintype "unspecified"))
    )
    (net (code "91") (name "Net-(Y1-OSC1)") (class "Default")
      (node (ref "C13") (pin "1") (pinfunction "1_1") (pintype "unspecified"))
      (node (ref "U2") (pin "8") (pinfunction "8_8") (pintype "unspecified"))
      (node (ref "Y1") (pin "1") (pinfunction "OSC1_1") (pintype "unspecified"))
    )
    (net (code "92") (name "Net-(Y1-OSC2)") (class "Default")
      (node (ref "C11") (pin "1") (pinfunction "1_1") (pintype "unspecified"))
      (node (ref "U2") (pin "7") (pinfunction "7_7") (pintype "unspecified"))
      (node (ref "Y1") (pin "2") (pinfunction "OSC2_2") (pintype "unspecified"))
    )
    (net (code "93") (name "VCC") (class "Default")
      (node (ref "C12") (pin "2") (pinfunction "2_2") (pintype "unspecified"))
      (node (ref "C2") (pin "2") (pinfunction "2_2") (pintype "unspecified"))
      (node (ref "C34") (pin "1") (pinfunction "1_1") (pintype "unspecified"))
      (node (ref "C35") (pin "1") (pinfunction "1_1") (pintype "unspecified"))
      (node (ref "C9") (pin "1") (pinfunction "1_1") (pintype "unspecified"))
      (node (ref "D1") (pin "2") (pinfunction "2_2") (pintype "unspecified"))
      (node (ref "D5") (pin "1") (pinfunction "1_1") (pintype "unspecified"))
      (node (ref "DZ2") (pin "2") (pinfunction "2_2") (pintype "unspecified"))
      (node (ref "J1") (pin "3") (pinfunction "3_3") (pintype "unspecified"))
      (node (ref "R15") (pin "1") (pinfunction "1_1") (pintype "unspecified"))
      (node (ref "R16") (pin "1") (pinfunction "1_1") (pintype "unspecified"))
      (node (ref "R33") (pin "1") (pinfunction "1_1") (pintype "unspecified"))
      (node (ref "R34") (pin "1") (pinfunction "1_1") (pintype "unspecified"))
      (node (ref "U1") (pin "1") (pinfunction "VOUT_1") (pintype "unspecified"))
      (node (ref "U3") (pin "3") (pinfunction "IN_3") (pintype "unspecified"))
      (node (ref "U8") (pin "15") (pinfunction "VDD_15") (pintype "unspecified"))
      (node (ref "U9") (pin "15") (pinfunction "VDD_15") (pintype "unspecified"))
    )
    (net (code "94") (name "VM") (class "Default")
      (node (ref "C23") (pin "2") (pinfunction "2_2") (pintype "unspecified"))
      (node (ref "C24") (pin "1") (pintype "unspecified"))
      (node (ref "C25") (pin "2") (pinfunction "2_2") (pintype "unspecified"))
      (node (ref "C26") (pin "1") (pintype "unspecified"))
      (node (ref "C30") (pin "2") (pinfunction "2_2") (pintype "unspecified"))
      (node (ref "C31") (pin "2") (pinfunction "2_2") (pintype "unspecified"))
      (node (ref "C6") (pin "1") (pintype "unspecified"))
      (node (ref "D2") (pin "1") (pinfunction "1_1") (pintype "unspecified"))
      (node (ref "DZ3") (pin "2") (pinfunction "2_2") (pintype "unspecified"))
      (node (ref "P1") (pin "4") (pinfunction "4_4") (pintype "unspecified"))
      (node (ref "P3") (pin "1") (pinfunction "1_1") (pintype "unspecified"))
      (node (ref "R22") (pin "2") (pinfunction "2_2") (pintype "unspecified"))
      (node (ref "R45") (pin "1") (pinfunction "1_1") (pintype "unspecified"))
      (node (ref "U8") (pin "22") (pinfunction "VBB1_22") (pintype "unspecified"))
      (node (ref "U8") (pin "28") (pinfunction "VBB2_28") (pintype "unspecified"))
      (node (ref "U9") (pin "22") (pinfunction "VBB1_22") (pintype "unspecified"))
      (node (ref "U9") (pin "28") (pinfunction "VBB2_28") (pintype "unspecified"))
    )
    (net (code "95") (name "VUSB") (class "Default")
      (node (ref "C1") (pin "2") (pinfunction "2_2") (pintype "unspecified"))
      (node (ref "C3") (pin "1") (pinfunction "1_1") (pintype "unspecified"))
      (node (ref "D1") (pin "1") (pinfunction "1_1") (pintype "unspecified"))
      (node (ref "P2") (pin "A4") (pinfunction "VBUS_A4") (pintype "unspecified"))
      (node (ref "P2") (pin "A9") (pinfunction "VBUS_A9") (pintype "unspecified"))
      (node (ref "P2") (pin "B4") (pinfunction "VBUS_B4") (pintype "unspecified"))
      (node (ref "P2") (pin "B9") (pinfunction "VBUS_B9") (pintype "unspecified"))
      (node (ref "R21") (pin "1") (pinfunction "1_1") (pintype "unspecified"))
      (node (ref "U2") (pin "16") (pinfunction "16_16") (pintype "unspecified"))
      (node (ref "U4") (pin "5") (pinfunction "5_5") (pintype "unspecified"))
    )
    (net (code "96") (name "unconnected-(P2-CC1-PadA5)") (class "Default")
      (node (ref "P2") (pin "A5") (pinfunction "CC1_A5") (pintype "unspecified"))
    )
    (net (code "97") (name "unconnected-(P2-CC2-PadB5)") (class "Default")
      (node (ref "P2") (pin "B5") (pinfunction "CC2_B5") (pintype "unspecified"))
    )
    (net (code "98") (name "unconnected-(P2-SUB1-PadA8)") (class "Default")
      (node (ref "P2") (pin "A8") (pinfunction "SUB1_A8") (pintype "unspecified"))
    )
    (net (code "99") (name "unconnected-(P2-SUB2-PadB8)") (class "Default")
      (node (ref "P2") (pin "B8") (pinfunction "SUB2_B8") (pintype "unspecified"))
    )
    (net (code "100") (name "unconnected-(P4-Pad5)") (class "Default")
      (node (ref "P4") (pin "5") (pinfunction "5_5") (pintype "unspecified"))
    )
    (net (code "101") (name "unconnected-(P10-Pad2)") (class "Default")
      (node (ref "P10") (pin "2") (pinfunction "2_2") (pintype "unspecified"))
    )
    (net (code "102") (name "unconnected-(P10-Pad8)") (class "Default")
      (node (ref "P10") (pin "8") (pinfunction "8_8") (pintype "unspecified"))
    )
    (net (code "103") (name "unconnected-(U2-Pad9)") (class "Default")
      (node (ref "U2") (pin "9") (pinfunction "9_9") (pintype "unspecified"))
    )
    (net (code "104") (name "unconnected-(U2-Pad10)") (class "Default")
      (node (ref "U2") (pin "10") (pinfunction "10_10") (pintype "unspecified"))
    )
    (net (code "105") (name "unconnected-(U2-Pad11)") (class "Default")
      (node (ref "U2") (pin "11") (pinfunction "11_11") (pintype "unspecified"))
    )
    (net (code "106") (name "unconnected-(U2-Pad12)") (class "Default")
      (node (ref "U2") (pin "12") (pinfunction "12_12") (pintype "unspecified"))
    )
    (net (code "107") (name "unconnected-(U2-Pad14)") (class "Default")
      (node (ref "U2") (pin "14") (pinfunction "14_14") (pintype "unspecified"))
    )
    (net (code "108") (name "unconnected-(U2-Pad15)") (class "Default")
      (node (ref "U2") (pin "15") (pinfunction "15_15") (pintype "unspecified"))
    )
    (net (code "109") (name "unconnected-(U5-PA11-Pad32)") (class "Default")
      (node (ref "U5") (pin "32") (pinfunction "PA11_32") (pintype "bidirectional"))
    )
    (net (code "110") (name "unconnected-(U5-PA12-Pad33)") (class "Default")
      (node (ref "U5") (pin "33") (pinfunction "PA12_33") (pintype "bidirectional"))
    )
    (net (code "111") (name "unconnected-(U5-PC13-TAMPER-RTC-Pad2)") (class "Default")
      (node (ref "U5") (pin "2") (pinfunction "PC13-TAMPER-RTC_2") (pintype "bidirectional"))
    )
    (net (code "112") (name "unconnected-(U5-VBAT-Pad1)") (class "Default")
      (node (ref "U5") (pin "1") (pinfunction "VBAT_1") (pintype "unspecified"))
    )
    (net (code "113") (name "unconnected-(U8-NC-Pad7)") (class "Default")
      (node (ref "U8") (pin "7") (pinfunction "NC_7") (pintype "unspecified"))
    )
    (net (code "114") (name "unconnected-(U8-NC-Pad20)") (class "Default")
      (node (ref "U8") (pin "20") (pinfunction "NC_20") (pintype "unspecified"))
    )
    (net (code "115") (name "unconnected-(U8-NC-Pad25)") (class "Default")
      (node (ref "U8") (pin "25") (pinfunction "NC_25") (pintype "unspecified"))
    )
    (net (code "116") (name "unconnected-(U9-NC-Pad7)") (class "Default")
      (node (ref "U9") (pin "7") (pinfunction "NC_7") (pintype "unspecified"))
    )
    (net (code "117") (name "unconnected-(U9-NC-Pad20)") (class "Default")
      (node (ref "U9") (pin "20") (pinfunction "NC_20") (pintype "unspecified"))
    )
    (net (code "118") (name "unconnected-(U9-NC-Pad25)") (class "Default")
      (node (ref "U9") (pin "25") (pinfunction "NC_25") (pintype "unspecified"))
    )
  )
)
